# Sheet2.net
KiCad netlist of a schematic drawn in Altium Designer
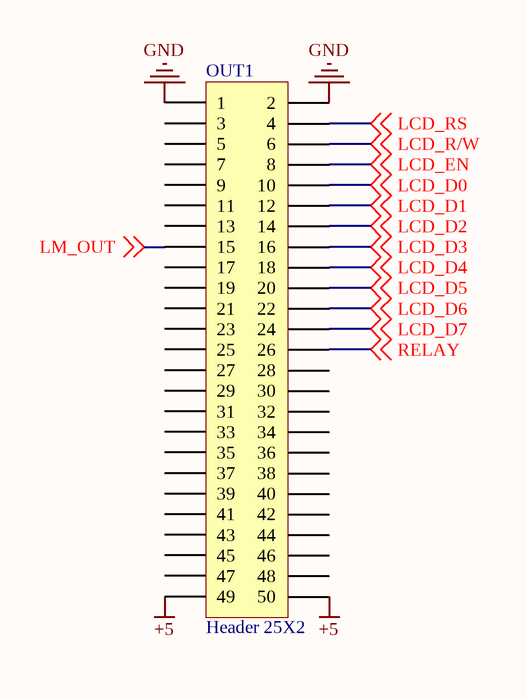
[diagram p0: Sheet2.SchDoc]

(export (version "E")
  (design (tool "Eeschema 10.0.6"))
  (components
    (comp (ref "OUT1")
      (value "Header 25X2")
      (footprint "HDR2X25")
      (description "Header, 25-Pin, Dual row")
      (fields (field (name "PUBLISHER") "Altium Limited"))
      (libsource (lib "Miscellaneous Connectors") (part "Header 25X2"))
    )
  )
  (nets
    (net (code "1") (name "+5") (class "Default")
      (node (ref "OUT1") (pin "49") (pinfunction "49_49") (pintype "passive"))
      (node (ref "OUT1") (pin "50") (pinfunction "50_50") (pintype "passive"))
    )
    (net (code "2") (name "GND") (class "Default")
      (node (ref "OUT1") (pin "1") (pinfunction "1_1") (pintype "passive"))
      (node (ref "OUT1") (pin "2") (pinfunction "2_2") (pintype "passive"))
    )
    (net (code "3") (name "LCD_D0") (class "Default")
      (node (ref "OUT1") (pin "10") (pinfunction "10_10") (pintype "passive"))
    )
    (net (code "4") (name "LCD_D1") (class "Default")
      (node (ref "OUT1") (pin "12") (pinfunction "12_12") (pintype "passive"))
    )
    (net (code "5") (name "LCD_D2") (class "Default")
      (node (ref "OUT1") (pin "14") (pinfunction "14_14") (pintype "passive"))
    )
    (net (code "6") (name "LCD_D3") (class "Default")
      (node (ref "OUT1") (pin "16") (pinfunction "16_16") (pintype "passive"))
    )
    (net (code "7") (name "LCD_D4") (class "Default")
      (node (ref "OUT1") (pin "18") (pinfunction "18_18") (pintype "passive"))
    )
    (net (code "8") (name "LCD_D5") (class "Default")
      (node (ref "OUT1") (pin "20") (pinfunction "20_20") (pintype "passive"))
    )
    (net (code "9") (name "LCD_D6") (class "Default")
      (node (ref "OUT1") (pin "22") (pinfunction "22_22") (pintype "passive"))
    )
    (net (code "10") (name "LCD_D7") (class "Default")
      (node (ref "OUT1") (pin "24") (pinfunction "24_24") (pintype "passive"))
    )
    (net (code "11") (name "LCD_EN") (class "Default")
      (node (ref "OUT1") (pin "8") (pinfunction "8_8") (pintype "passive"))
    )
    (net (code "12") (name "LCD_RS") (class "Default")
      (node (ref "OUT1") (pin "4") (pinfunction "4_4") (pintype "passive"))
    )
    (net (code "13") (name "LCD_R{slash}W") (class "Default")
      (node (ref "OUT1") (pin "6") (pinfunction "6_6") (pintype "passive"))
    )
    (net (code "14") (name "LM_OUT") (class "Default")
      (node (ref "OUT1") (pin "15") (pinfunction "15_15") (pintype "passive"))
    )
    (net (code "15") (name "RELAY") (class "Default")
      (node (ref "OUT1") (pin "26") (pinfunction "26_26") (pintype "passive"))
    )
    (net (code "16") (name "unconnected-(OUT1-Pad3)") (class "Default")
      (node (ref "OUT1") (pin "3") (pinfunction "3_3") (pintype "passive"))
    )
    (net (code "17") (name "unconnected-(OUT1-Pad5)") (class "Default")
      (node (ref "OUT1") (pin "5") (pinfunction "5_5") (pintype "passive"))
    )
    (net (code "18") (name "unconnected-(OUT1-Pad7)") (class "Default")
      (node (ref "OUT1") (pin "7") (pinfunction "7_7") (pintype "passive"))
    )
    (net (code "19") (name "unconnected-(OUT1-Pad9)") (class "Default")
      (node (ref "OUT1") (pin "9") (pinfunction "9_9") (pintype "passive"))
    )
    (net (code "20") (name "unconnected-(OUT1-Pad11)") (class "Default")
      (node (ref "OUT1") (pin "11") (pinfunction "11_11") (pintype "passive"))
    )
    (net (code "21") (name "unconnected-(OUT1-Pad13)") (class "Default")
      (node (ref "OUT1") (pin "13") (pinfunction "13_13") (pintype "passive"))
    )
    (net (code "22") (name "unconnected-(OUT1-Pad17)") (class "Default")
      (node (ref "OUT1") (pin "17") (pinfunction "17_17") (pintype "passive"))
    )
    (net (code "23") (name "unconnected-(OUT1-Pad19)") (class "Default")
      (node (ref "OUT1") (pin "19") (pinfunction "19_19") (pintype "passive"))
    )
    (net (code "24") (name "unconnected-(OUT1-Pad21)") (class "Default")
      (node (ref "OUT1") (pin "21") (pinfunction "21_21") (pintype "passive"))
    )
    (net (code "25") (name "unconnected-(OUT1-Pad23)") (class "Default")
      (node (ref "OUT1") (pin "23") (pinfunction "23_23") (pintype "passive"))
    )
    (net (code "26") (name "unconnected-(OUT1-Pad25)") (class "Default")
      (node (ref "OUT1") (pin "25") (pinfunction "25_25") (pintype "passive"))
    )
    (net (code "27") (name "unconnected-(OUT1-Pad27)") (class "Default")
      (node (ref "OUT1") (pin "27") (pinfunction "27_27") (pintype "passive"))
    )
    (net (code "28") (name "unconnected-(OUT1-Pad28)") (class "Default")
      (node (ref "OUT1") (pin "28") (pinfunction "28_28") (pintype "passive"))
    )
    (net (code "29") (name "unconnected-(OUT1-Pad29)") (class "Default")
      (node (ref "OUT1") (pin "29") (pinfunction "29_29") (pintype "passive"))
    )
    (net (code "30") (name "unconnected-(OUT1-Pad30)") (class "Default")
      (node (ref "OUT1") (pin "30") (pinfunction "30_30") (pintype "passive"))
    )
    (net (code "31") (name "unconnected-(OUT1-Pad31)") (class "Default")
      (node (ref "OUT1") (pin "31") (pinfunction "31_31") (pintype "passive"))
    )
    (net (code "32") (name "unconnected-(OUT1-Pad32)") (class "Default")
      (node (ref "OUT1") (pin "32") (pinfunction "32_32") (pintype "passive"))
    )
    (net (code "33") (name "unconnected-(OUT1-Pad33)") (class "Default")
      (node (ref "OUT1") (pin "33") (pinfunction "33_33") (pintype "passive"))
    )
    (net (code "34") (name "unconnected-(OUT1-Pad34)") (class "Default")
      (node (ref "OUT1") (pin "34") (pinfunction "34_34") (pintype "passive"))
    )
    (net (code "35") (name "unconnected-(OUT1-Pad35)") (class "Default")
      (node (ref "OUT1") (pin "35") (pinfunction "35_35") (pintype "passive"))
    )
    (net (code "36") (name "unconnected-(OUT1-Pad36)") (class "Default")
      (node (ref "OUT1") (pin "36") (pinfunction "36_36") (pintype "passive"))
    )
    (net (code "37") (name "unconnected-(OUT1-Pad37)") (class "Default")
      (node (ref "OUT1") (pin "37") (pinfunction "37_37") (pintype "passive"))
    )
    (net (code "38") (name "unconnected-(OUT1-Pad38)") (class "Default")
      (node (ref "OUT1") (pin "38") (pinfunction "38_38") (pintype "passive"))
    )
    (net (code "39") (name "unconnected-(OUT1-Pad39)") (class "Default")
      (node (ref "OUT1") (pin "39") (pinfunction "39_39") (pintype "passive"))
    )
    (net (code "40") (name "unconnected-(OUT1-Pad40)") (class "Default")
      (node (ref "OUT1") (pin "40") (pinfunction "40_40") (pintype "passive"))
    )
    (net (code "41") (name "unconnected-(OUT1-Pad41)") (class "Default")
      (node (ref "OUT1") (pin "41") (pinfunction "41_41") (pintype "passive"))
    )
    (net (code "42") (name "unconnected-(OUT1-Pad42)") (class "Default")
      (node (ref "OUT1") (pin "42") (pinfunction "42_42") (pintype "passive"))
    )
    (net (code "43") (name "unconnected-(OUT1-Pad43)") (class "Default")
      (node (ref "OUT1") (pin "43") (pinfunction "43_43") (pintype "passive"))
    )
    (net (code "44") (name "unconnected-(OUT1-Pad44)") (class "Default")
      (node (ref "OUT1") (pin "44") (pinfunction "44_44") (pintype "passive"))
    )
    (net (code "45") (name "unconnected-(OUT1-Pad45)") (class "Default")
      (node (ref "OUT1") (pin "45") (pinfunction "45_45") (pintype "passive"))
    )
    (net (code "46") (name "unconnected-(OUT1-Pad46)") (class "Default")
      (node (ref "OUT1") (pin "46") (pinfunction "46_46") (pintype "passive"))
    )
    (net (code "47") (name "unconnected-(OUT1-Pad47)") (class "Default")
      (node (ref "OUT1") (pin "47") (pinfunction "47_47") (pintype "passive"))
    )
    (net (code "48") (name "unconnected-(OUT1-Pad48)") (class "Default")
      (node (ref "OUT1") (pin "48") (pinfunction "48_48") (pintype "passive"))
    )
  )
)
